# Spirit.net
KiCad netlist of a schematic drawn in EAGLE
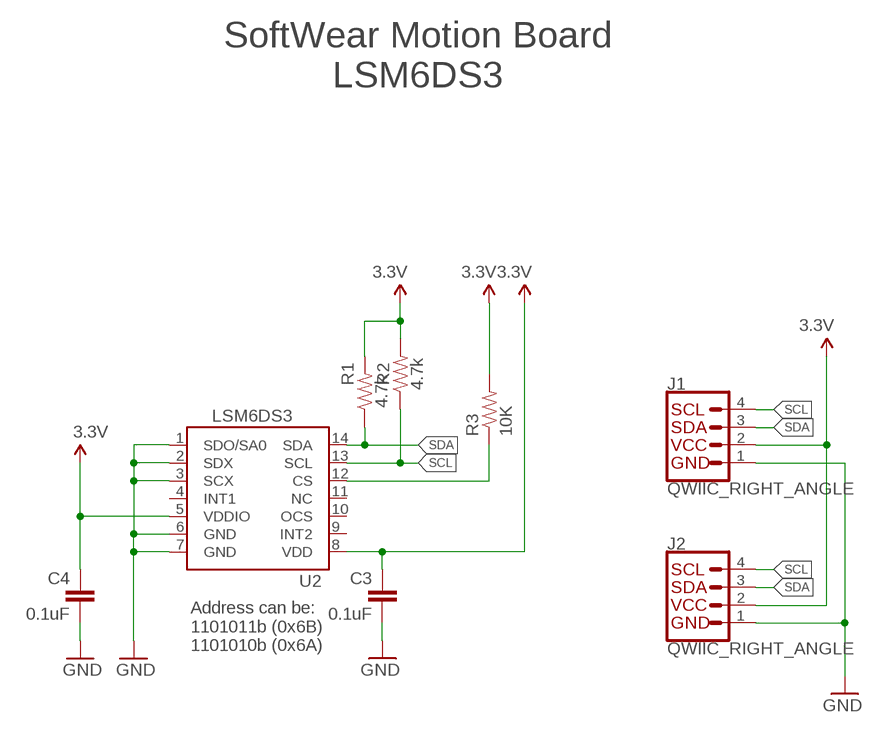
[diagram p0: schematic, sheet 1]

(export (version "E")
  (design (tool "Eeschema 10.0.6"))
  (components
    (comp (ref "C3")
      (value "0.1uF")
      (footprint "eagle-import:0603-CAP")
      (libsource (lib "eagle-import") (part "0.1UF-100V-10%(0603)"))
    )
    (comp (ref "C4")
      (value "0.1uF")
      (footprint "eagle-import:0603-CAP")
      (libsource (lib "eagle-import") (part "0.1UF-100V-10%(0603)"))
    )
    (comp (ref "J1")
      (value "QWIIC_RIGHT_ANGLE")
      (footprint "eagle-import:JST04_1MM_RA")
      (libsource (lib "eagle-import") (part "QWIIC_CONNECTORJS-1MM"))
    )
    (comp (ref "J2")
      (value "QWIIC_RIGHT_ANGLE")
      (footprint "eagle-import:JST04_1MM_RA")
      (libsource (lib "eagle-import") (part "QWIIC_CONNECTORJS-1MM"))
    )
    (comp (ref "R1")
      (value "4.7k")
      (footprint "eagle-import:0603")
      (libsource (lib "eagle-import") (part "4.7KOHM-0603-1/10W-1%"))
    )
    (comp (ref "R2")
      (value "4.7k")
      (footprint "eagle-import:0603")
      (libsource (lib "eagle-import") (part "4.7KOHM-0603-1/10W-1%"))
    )
    (comp (ref "R3")
      (value "10K")
      (footprint "eagle-import:0603-RES")
      (libsource (lib "eagle-import") (part "10KOHM-1/10W-1%(0603)0603"))
    )
    (comp (ref "U2")
      (value "LSM6DS3")
      (footprint "eagle-import:LGA14L_DOT_INDICATOR")
      (libsource (lib "eagle-import") (part "LSM6DS3DOT_INDICATION"))
    )
  )
  (nets
    (net (code "1") (name "3.3V") (class "Default")
      (node (ref "C3") (pin "1") (pinfunction "1_1") (pintype "passive"))
      (node (ref "C4") (pin "1") (pinfunction "1_1") (pintype "passive"))
      (node (ref "J1") (pin "2") (pinfunction "2_2") (pintype "power_in"))
      (node (ref "J2") (pin "2") (pinfunction "2_2") (pintype "power_in"))
      (node (ref "R1") (pin "2") (pinfunction "2_2") (pintype "passive"))
      (node (ref "R2") (pin "2") (pinfunction "2_2") (pintype "passive"))
      (node (ref "R3") (pin "2") (pinfunction "2_2") (pintype "passive"))
      (node (ref "U2") (pin "5") (pinfunction "VDDIO_5") (pintype "bidirectional"))
      (node (ref "U2") (pin "8") (pinfunction "VDD_8") (pintype "bidirectional"))
    )
    (net (code "2") (name "GND") (class "Default")
      (node (ref "C3") (pin "2") (pinfunction "2_2") (pintype "passive"))
      (node (ref "C4") (pin "2") (pinfunction "2_2") (pintype "passive"))
      (node (ref "J1") (pin "1") (pinfunction "1_1") (pintype "power_in"))
      (node (ref "J2") (pin "1") (pinfunction "1_1") (pintype "power_in"))
      (node (ref "U2") (pin "1") (pinfunction "SDO/SA0_1") (pintype "bidirectional"))
      (node (ref "U2") (pin "2") (pinfunction "SDX_2") (pintype "bidirectional"))
      (node (ref "U2") (pin "3") (pinfunction "SCX_3") (pintype "bidirectional"))
      (node (ref "U2") (pin "6") (pinfunction "GND_6") (pintype "bidirectional"))
      (node (ref "U2") (pin "7") (pinfunction "GND_7") (pintype "bidirectional"))
    )
    (net (code "3") (name "Net-(U2-CS)") (class "Default")
      (node (ref "R3") (pin "1") (pinfunction "1_1") (pintype "passive"))
      (node (ref "U2") (pin "12") (pinfunction "CS_12") (pintype "bidirectional"))
    )
    (net (code "4") (name "SCL") (class "Default")
      (node (ref "J1") (pin "4") (pinfunction "4_4") (pintype "passive"))
      (node (ref "J2") (pin "4") (pinfunction "4_4") (pintype "passive"))
      (node (ref "R2") (pin "1") (pinfunction "1_1") (pintype "passive"))
      (node (ref "U2") (pin "13") (pinfunction "SCL_13") (pintype "bidirectional"))
    )
    (net (code "5") (name "SDA") (class "Default")
      (node (ref "J1") (pin "3") (pinfunction "3_3") (pintype "passive"))
      (node (ref "J2") (pin "3") (pinfunction "3_3") (pintype "passive"))
      (node (ref "R1") (pin "1") (pinfunction "1_1") (pintype "passive"))
      (node (ref "U2") (pin "14") (pinfunction "SDA_14") (pintype "bidirectional"))
    )
    (net (code "6") (name "unconnected-(U2-INT1-Pad4)") (class "Default")
      (node (ref "U2") (pin "4") (pinfunction "INT1_4") (pintype "bidirectional"))
    )
    (net (code "7") (name "unconnected-(U2-INT2-Pad9)") (class "Default")
      (node (ref "U2") (pin "9") (pinfunction "INT2_9") (pintype "bidirectional"))
    )
    (net (code "8") (name "unconnected-(U2-NC-Pad11)") (class "Default")
      (node (ref "U2") (pin "11") (pinfunction "NC_11") (pintype "bidirectional"))
    )
    (net (code "9") (name "unconnected-(U2-OCS-Pad10)") (class "Default")
      (node (ref "U2") (pin "10") (pinfunction "OCS_10") (pintype "bidirectional"))
    )
  )
)
